# Sheet1.net
KiCad netlist of a schematic drawn in Altium Designer
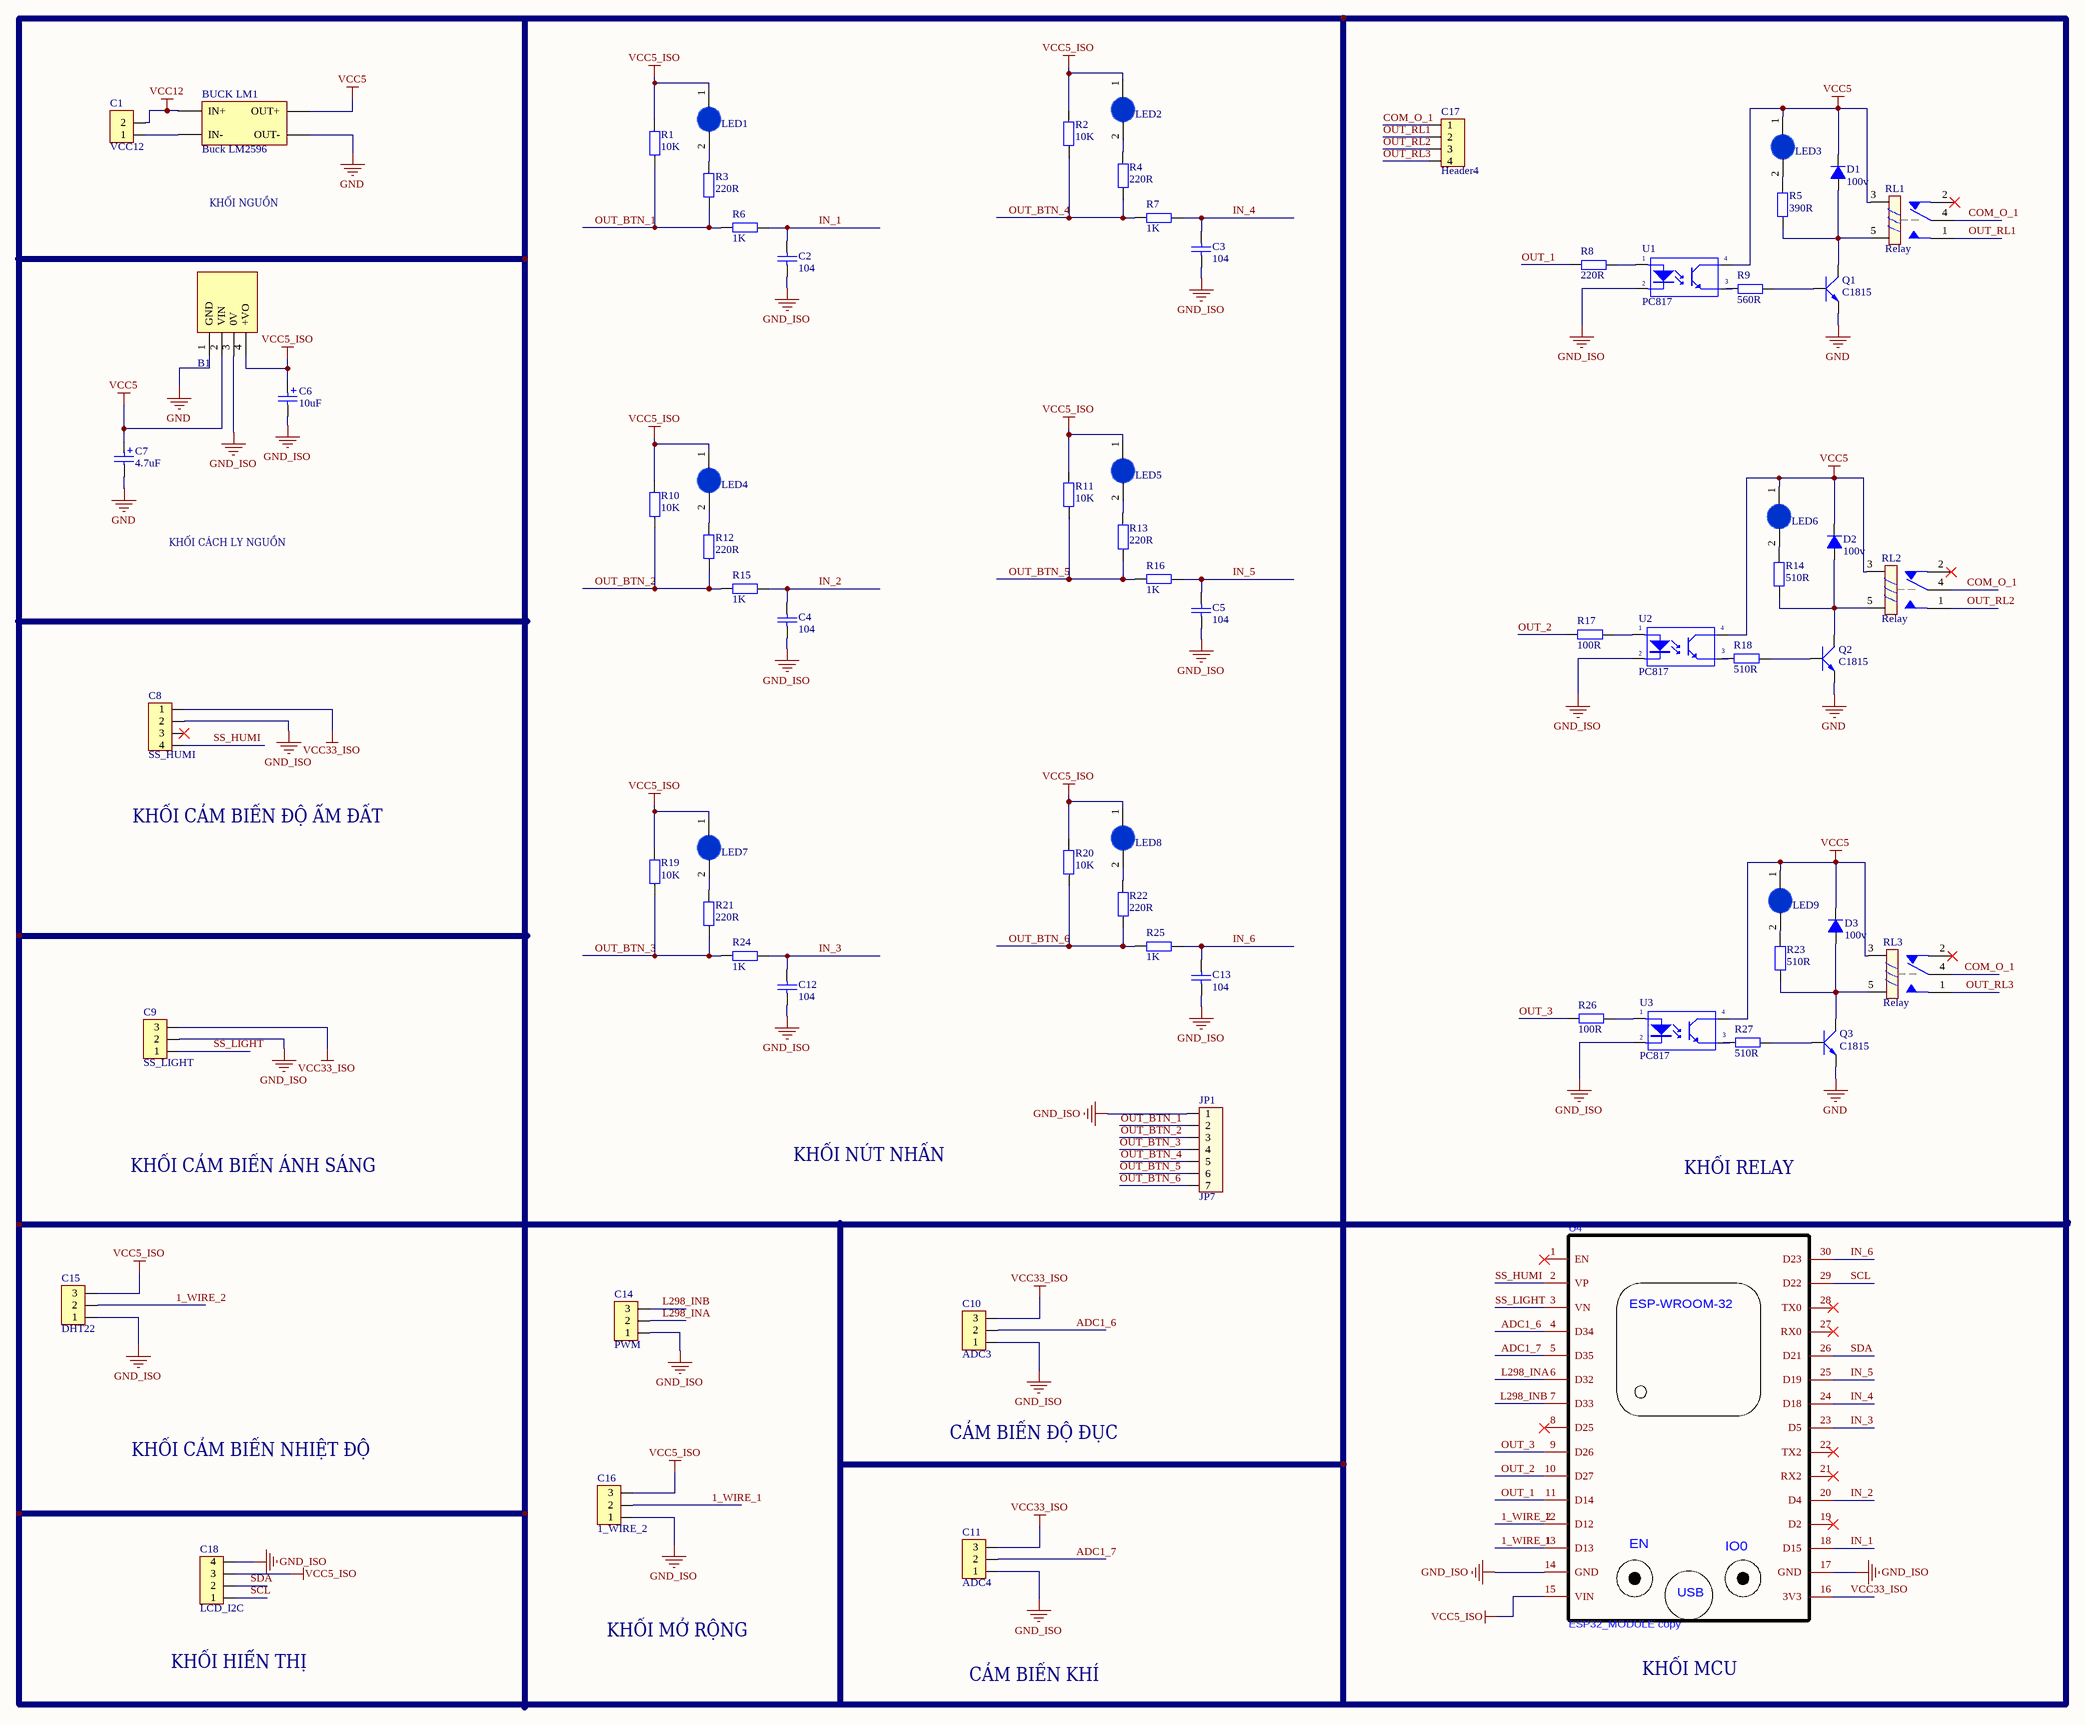
[diagram p0: Sheet1.SchDoc]

(export (version "E")
  (design (tool "Eeschema 10.0.6"))
  (components
    (comp (ref "B1")
      (value "B0505S1W")
      (footprint "B0505S1W")
      (description "Power Supply")
      (fields (field (name "MANUFACTURER_PART_NUMBER") "B0505S-1W"))
      (libsource (lib "myLib_v1") (part "B0505S1W"))
    )
    (comp (ref "BUCK LM1")
      (value "Buck LM2596")
      (footprint "BUCK LM2596")
      (libsource (lib "myLib_v1") (part "Buck LM2596"))
    )
    (comp (ref "C1")
      (value "VCC12")
      (footprint "Header2")
      (description "Header IDC, 2 x 1 Pin Vertical 2.54mm Pitch (Non-Boxed, Male)")
      (fields
        (field (name "MANUFACTURER") "Würth Elektronik eiSos GmbH")
        (field (name "PARTNO") "613002143121")
        (field (name "CREATED BY") "Karrer Zheng")
      )
      (libsource (lib "myLib_v1") (part "Header2"))
    )
    (comp (ref "C2")
      (value "104")
      (footprint "tu gom")
      (description "Cắm")
      (libsource (lib "Altium_Lib_by_KhueNguyenCreator") (part "Tu gom 104 50V"))
    )
    (comp (ref "C3")
      (value "104")
      (footprint "tu gom")
      (description "Cắm")
      (libsource (lib "Altium_Lib_by_KhueNguyenCreator") (part "Tu gom 104 50V"))
    )
    (comp (ref "C4")
      (value "104")
      (footprint "tu gom")
      (description "Cắm")
      (libsource (lib "Altium_Lib_by_KhueNguyenCreator") (part "Tu gom 104 50V"))
    )
    (comp (ref "C5")
      (value "104")
      (footprint "tu gom")
      (description "Cắm")
      (libsource (lib "Altium_Lib_by_KhueNguyenCreator") (part "Tu gom 104 50V"))
    )
    (comp (ref "C6")
      (value "10uF")
      (footprint "CP2/5")
      (description "Polarized Capacitor (Surface Mount)")
      (fields (field (name "Comment") "Cap Pol3") (field (name "PUBLISHER") "Altium Limited"))
      (libsource (lib "myLib_v1") (part "Cap Pol3"))
    )
    (comp (ref "C7")
      (value "4.7uF")
      (footprint "CP2/5")
      (description "Polarized Capacitor (Surface Mount)")
      (fields (field (name "Comment") "Cap Pol3") (field (name "PUBLISHER") "Altium Limited"))
      (libsource (lib "myLib_v1") (part "Cap Pol3"))
    )
    (comp (ref "C8")
      (value "SS_HUMI")
      (footprint "Header4")
      (description "Header IDC, 4 x 1 Pin Vertical 2.54mm Pitch (Non-Boxed, Male)")
      (fields
        (field (name "MANUFACTURER") "Würth Elektronik eiSos GmbH")
        (field (name "PARTNO") "613002143121")
        (field (name "CREATED BY") "Karrer Zheng")
      )
      (libsource (lib "myLib_v1") (part "Header4"))
    )
    (comp (ref "C9")
      (value "SS_LIGHT")
      (footprint "Header3")
      (description "Header IDC, 3 x 1 Pin Vertical 2.54mm Pitch (Non-Boxed, Male)")
      (fields
        (field (name "MANUFACTURER") "Würth Elektronik eiSos GmbH")
        (field (name "PARTNO") "613002143121")
        (field (name "CREATED BY") "Karrer Zheng")
      )
      (libsource (lib "myLib_v1") (part "Header3"))
    )
    (comp (ref "C10")
      (value "ADC3")
      (footprint "Header3")
      (description "Header IDC, 3 x 1 Pin Vertical 2.54mm Pitch (Non-Boxed, Male)")
      (fields
        (field (name "MANUFACTURER") "Würth Elektronik eiSos GmbH")
        (field (name "PARTNO") "613002143121")
        (field (name "CREATED BY") "Karrer Zheng")
      )
      (libsource (lib "myLib_v1") (part "Header3"))
    )
    (comp (ref "C11")
      (value "ADC4")
      (footprint "Header3")
      (description "Header IDC, 3 x 1 Pin Vertical 2.54mm Pitch (Non-Boxed, Male)")
      (fields
        (field (name "MANUFACTURER") "Würth Elektronik eiSos GmbH")
        (field (name "PARTNO") "613002143121")
        (field (name "CREATED BY") "Karrer Zheng")
      )
      (libsource (lib "myLib_v1") (part "Header3"))
    )
    (comp (ref "C12")
      (value "104")
      (footprint "tu gom")
      (description "Cắm")
      (libsource (lib "Altium_Lib_by_KhueNguyenCreator") (part "Tu gom 104 50V"))
    )
    (comp (ref "C13")
      (value "104")
      (footprint "tu gom")
      (description "Cắm")
      (libsource (lib "Altium_Lib_by_KhueNguyenCreator") (part "Tu gom 104 50V"))
    )
    (comp (ref "C14")
      (value "PWM")
      (footprint "Header3")
      (description "Header IDC, 3 x 1 Pin Vertical 2.54mm Pitch (Non-Boxed, Male)")
      (fields
        (field (name "MANUFACTURER") "Würth Elektronik eiSos GmbH")
        (field (name "PARTNO") "613002143121")
        (field (name "CREATED BY") "Karrer Zheng")
      )
      (libsource (lib "myLib_v1") (part "Header3"))
    )
    (comp (ref "C15")
      (value "DHT22")
      (footprint "Header3")
      (description "Header IDC, 3 x 1 Pin Vertical 2.54mm Pitch (Non-Boxed, Male)")
      (fields
        (field (name "MANUFACTURER") "Würth Elektronik eiSos GmbH")
        (field (name "PARTNO") "613002143121")
        (field (name "CREATED BY") "Karrer Zheng")
      )
      (libsource (lib "myLib_v1") (part "Header3"))
    )
    (comp (ref "C16")
      (value "1_WIRE_2")
      (footprint "Header3")
      (description "Header IDC, 3 x 1 Pin Vertical 2.54mm Pitch (Non-Boxed, Male)")
      (fields
        (field (name "MANUFACTURER") "Würth Elektronik eiSos GmbH")
        (field (name "PARTNO") "613002143121")
        (field (name "CREATED BY") "Karrer Zheng")
      )
      (libsource (lib "myLib_v1") (part "Header3"))
    )
    (comp (ref "C17")
      (value "Header4")
      (footprint "Header4")
      (description "Header IDC, 4 x 1 Pin Vertical 2.54mm Pitch (Non-Boxed, Male)")
      (fields
        (field (name "MANUFACTURER") "Würth Elektronik eiSos GmbH")
        (field (name "PARTNO") "613002143121")
        (field (name "CREATED BY") "Karrer Zheng")
      )
      (libsource (lib "") (part "Header4_2"))
    )
    (comp (ref "C18")
      (value "LCD_I2C")
      (footprint "Header4")
      (description "Header IDC, 4 x 1 Pin Vertical 2.54mm Pitch (Non-Boxed, Male)")
      (fields
        (field (name "MANUFACTURER") "Würth Elektronik eiSos GmbH")
        (field (name "PARTNO") "613002143121")
        (field (name "CREATED BY") "Karrer Zheng")
      )
      (libsource (lib "") (part "Header4_1"))
    )
    (comp (ref "D1")
      (value "100v")
      (footprint "DIODE 0.5A")
      (description "Cắm")
      (libsource (lib "Altium_Lib_by_KhueNguyenCreator") (part "Diode 1N4148"))
    )
    (comp (ref "D2")
      (value "100v")
      (footprint "DIODE 0.5A")
      (description "Cắm")
      (libsource (lib "Altium_Lib_by_KhueNguyenCreator") (part "Diode 1N4148"))
    )
    (comp (ref "D3")
      (value "100v")
      (footprint "DIODE 0.5A")
      (description "Cắm")
      (libsource (lib "Altium_Lib_by_KhueNguyenCreator") (part "Diode 1N4148"))
    )
    (comp (ref "JP1")
      (value "JP7")
      (footprint "Header7")
      (description "Connector 7")
      (libsource (lib "myLib_v1") (part "Header7"))
    )
    (comp (ref "LED1")
      (value "LED 3mm")
      (footprint "LED-3MM-BLUE")
      (description "Cắm")
      (libsource (lib "myLib_v1") (part "LED 3mm Xanh Duong"))
    )
    (comp (ref "LED2")
      (value "LED 3mm")
      (footprint "LED-3MM-BLUE")
      (description "Cắm")
      (libsource (lib "myLib_v1") (part "LED 3mm Xanh Duong"))
    )
    (comp (ref "LED3")
      (value "LED 3mm")
      (footprint "LED-3MM-BLUE")
      (description "Cắm")
      (libsource (lib "myLib_v1") (part "LED 3mm Xanh Duong"))
    )
    (comp (ref "LED4")
      (value "LED 3mm")
      (footprint "LED-3MM-BLUE")
      (description "Cắm")
      (libsource (lib "myLib_v1") (part "LED 3mm Xanh Duong"))
    )
    (comp (ref "LED5")
      (value "LED 3mm")
      (footprint "LED-3MM-BLUE")
      (description "Cắm")
      (libsource (lib "myLib_v1") (part "LED 3mm Xanh Duong"))
    )
    (comp (ref "LED6")
      (value "LED 3mm")
      (footprint "LED-3MM-BLUE")
      (description "Cắm")
      (libsource (lib "myLib_v1") (part "LED 3mm Xanh Duong"))
    )
    (comp (ref "LED7")
      (value "LED 3mm")
      (footprint "LED-3MM-BLUE")
      (description "Cắm")
      (libsource (lib "myLib_v1") (part "LED 3mm Xanh Duong"))
    )
    (comp (ref "LED8")
      (value "LED 3mm")
      (footprint "LED-3MM-BLUE")
      (description "Cắm")
      (libsource (lib "myLib_v1") (part "LED 3mm Xanh Duong"))
    )
    (comp (ref "LED9")
      (value "LED 3mm")
      (footprint "LED-3MM-BLUE")
      (description "Cắm")
      (libsource (lib "myLib_v1") (part "LED 3mm Xanh Duong"))
    )
    (comp (ref "Q1")
      (value "C1815")
      (footprint "C1815_cam")
      (description "NPN 600mW, ECB")
      (libsource (lib "myLib_v1") (part "C1815"))
    )
    (comp (ref "Q2")
      (value "C1815")
      (footprint "C1815_cam")
      (description "NPN 600mW, ECB")
      (libsource (lib "myLib_v1") (part "C1815"))
    )
    (comp (ref "Q3")
      (value "C1815")
      (footprint "C1815_cam")
      (description "NPN 600mW, ECB")
      (libsource (lib "myLib_v1") (part "C1815"))
    )
    (comp (ref "R1")
      (value "10K")
      (footprint "R1/4W")
      (description "Resistor 1/4W")
      (libsource (lib "myLib_v1") (part "R1/4W"))
    )
    (comp (ref "R2")
      (value "10K")
      (footprint "R1/4W")
      (description "Resistor 1/4W")
      (libsource (lib "myLib_v1") (part "R1/4W"))
    )
    (comp (ref "R3")
      (value "220R")
      (footprint "R1/4W")
      (description "Resistor 1/4W")
      (libsource (lib "myLib_v1") (part "R1/4W"))
    )
    (comp (ref "R4")
      (value "220R")
      (footprint "R1/4W")
      (description "Resistor 1/4W")
      (libsource (lib "myLib_v1") (part "R1/4W"))
    )
    (comp (ref "R5")
      (value "390R")
      (footprint "R1/4W")
      (description "Resistor 1/4W")
      (libsource (lib "myLib_v1") (part "R1/4W"))
    )
    (comp (ref "R6")
      (value "1K")
      (footprint "R1/4W")
      (description "Resistor 1/4W")
      (libsource (lib "myLib_v1") (part "R1/4W"))
    )
    (comp (ref "R7")
      (value "1K")
      (footprint "R1/4W")
      (description "Resistor 1/4W")
      (libsource (lib "myLib_v1") (part "R1/4W"))
    )
    (comp (ref "R8")
      (value "220R")
      (footprint "R1/4W")
      (description "Resistor 1/4W")
      (libsource (lib "myLib_v1") (part "R1/4W"))
    )
    (comp (ref "R9")
      (value "560R")
      (footprint "R1/4W")
      (description "Resistor 1/4W")
      (libsource (lib "myLib_v1") (part "R1/4W"))
    )
    (comp (ref "R10")
      (value "10K")
      (footprint "R1/4W")
      (description "Resistor 1/4W")
      (libsource (lib "myLib_v1") (part "R1/4W"))
    )
    (comp (ref "R11")
      (value "10K")
      (footprint "R1/4W")
      (description "Resistor 1/4W")
      (libsource (lib "myLib_v1") (part "R1/4W"))
    )
    (comp (ref "R12")
      (value "220R")
      (footprint "R1/4W")
      (description "Resistor 1/4W")
      (libsource (lib "myLib_v1") (part "R1/4W"))
    )
    (comp (ref "R13")
      (value "220R")
      (footprint "R1/4W")
      (description "Resistor 1/4W")
      (libsource (lib "myLib_v1") (part "R1/4W"))
    )
    (comp (ref "R14")
      (value "510R")
      (footprint "R1/4W")
      (description "Resistor 1/4W")
      (libsource (lib "myLib_v1") (part "R1/4W"))
    )
    (comp (ref "R15")
      (value "1K")
      (footprint "R1/4W")
      (description "Resistor 1/4W")
      (libsource (lib "myLib_v1") (part "R1/4W"))
    )
    (comp (ref "R16")
      (value "1K")
      (footprint "R1/4W")
      (description "Resistor 1/4W")
      (libsource (lib "myLib_v1") (part "R1/4W"))
    )
    (comp (ref "R17")
      (value "100R")
      (footprint "R1/4W")
      (description "Resistor 1/4W")
      (libsource (lib "myLib_v1") (part "R1/4W"))
    )
    (comp (ref "R18")
      (value "510R")
      (footprint "R1/4W")
      (description "Resistor 1/4W")
      (libsource (lib "myLib_v1") (part "R1/4W"))
    )
    (comp (ref "R19")
      (value "10K")
      (footprint "R1/4W")
      (description "Resistor 1/4W")
      (libsource (lib "myLib_v1") (part "R1/4W"))
    )
    (comp (ref "R20")
      (value "10K")
      (footprint "R1/4W")
      (description "Resistor 1/4W")
      (libsource (lib "myLib_v1") (part "R1/4W"))
    )
    (comp (ref "R21")
      (value "220R")
      (footprint "R1/4W")
      (description "Resistor 1/4W")
      (libsource (lib "myLib_v1") (part "R1/4W"))
    )
    (comp (ref "R22")
      (value "220R")
      (footprint "R1/4W")
      (description "Resistor 1/4W")
      (libsource (lib "myLib_v1") (part "R1/4W"))
    )
    (comp (ref "R23")
      (value "510R")
      (footprint "R1/4W")
      (description "Resistor 1/4W")
      (libsource (lib "myLib_v1") (part "R1/4W"))
    )
    (comp (ref "R24")
      (value "1K")
      (footprint "R1/4W")
      (description "Resistor 1/4W")
      (libsource (lib "myLib_v1") (part "R1/4W"))
    )
    (comp (ref "R25")
      (value "1K")
      (footprint "R1/4W")
      (description "Resistor 1/4W")
      (libsource (lib "myLib_v1") (part "R1/4W"))
    )
    (comp (ref "R26")
      (value "100R")
      (footprint "R1/4W")
      (description "Resistor 1/4W")
      (libsource (lib "myLib_v1") (part "R1/4W"))
    )
    (comp (ref "R27")
      (value "510R")
      (footprint "R1/4W")
      (description "Resistor 1/4W")
      (libsource (lib "myLib_v1") (part "R1/4W"))
    )
    (comp (ref "RL1")
      (value "Relay")
      (footprint "RELAY_SRA_05VDC_SL_C")
      (description "Relay 5 Chan")
      (libsource (lib "myLib_v1") (part "RL_SRA-05VDC-SL-C"))
    )
    (comp (ref "RL2")
      (value "Relay")
      (footprint "RELAY_SRA_05VDC_SL_C")
      (description "Relay 5 Chan")
      (libsource (lib "myLib_v1") (part "RL_SRA-05VDC-SL-C"))
    )
    (comp (ref "RL3")
      (value "Relay")
      (footprint "RELAY_SRA_05VDC_SL_C")
      (description "Relay 5 Chan")
      (libsource (lib "myLib_v1") (part "RL_SRA-05VDC-SL-C"))
    )
    (comp (ref "U1")
      (value "PC817")
      (footprint "DIP4/W0.3")
      (description "Single Opto")
      (libsource (lib "myLib_v1") (part "PC817"))
    )
    (comp (ref "U2")
      (value "PC817")
      (footprint "DIP4/W0.3")
      (description "Single Opto")
      (libsource (lib "myLib_v1") (part "PC817"))
    )
    (comp (ref "U3")
      (value "PC817")
      (footprint "DIP4/W0.3")
      (description "Single Opto")
      (libsource (lib "myLib_v1") (part "PC817"))
    )
    (comp (ref "U4")
      (value "ESP32_MODULE copy")
      (footprint "ESP32-WIFIMODULE-FOOTPRINT")
      (libsource (lib "myLib_v1") (part "ESP32_MODULE copy"))
    )
  )
  (nets
    (net (code "1") (name "/1_WIRE_1") (class "Default")
      (node (ref "C16") (pin "2") (pinfunction "2_2") (pintype "passive"))
      (node (ref "U4") (pin "13") (pinfunction "D13_13") (pintype "passive"))
    )
    (net (code "2") (name "/1_WIRE_2") (class "Default")
      (node (ref "C15") (pin "2") (pinfunction "2_2") (pintype "passive"))
      (node (ref "U4") (pin "12") (pinfunction "D12_12") (pintype "passive"))
    )
    (net (code "3") (name "/ADC1_6") (class "Default")
      (node (ref "C10") (pin "2") (pinfunction "2_2") (pintype "passive"))
      (node (ref "U4") (pin "4") (pinfunction "D34_4") (pintype "passive"))
    )
    (net (code "4") (name "/ADC1_7") (class "Default")
      (node (ref "C11") (pin "2") (pinfunction "2_2") (pintype "passive"))
      (node (ref "U4") (pin "5") (pinfunction "D35_5") (pintype "passive"))
    )
    (net (code "5") (name "/COM_O_1") (class "Default")
      (node (ref "C17") (pin "1") (pinfunction "1_1") (pintype "passive"))
      (node (ref "RL1") (pin "4") (pinfunction "4_4") (pintype "passive"))
      (node (ref "RL2") (pin "4") (pinfunction "4_4") (pintype "passive"))
      (node (ref "RL3") (pin "4") (pinfunction "4_4") (pintype "passive"))
    )
    (net (code "6") (name "/IN_1") (class "Default")
      (node (ref "C2") (pin "1") (pinfunction "1_1") (pintype "passive"))
      (node (ref "R6") (pin "1") (pinfunction "1_1") (pintype "passive"))
      (node (ref "U4") (pin "18") (pinfunction "D15_18") (pintype "passive"))
    )
    (net (code "7") (name "/IN_2") (class "Default")
      (node (ref "C4") (pin "1") (pinfunction "1_1") (pintype "passive"))
      (node (ref "R15") (pin "1") (pinfunction "1_1") (pintype "passive"))
      (node (ref "U4") (pin "20") (pinfunction "D4_20") (pintype "passive"))
    )
    (net (code "8") (name "/IN_3") (class "Default")
      (node (ref "C12") (pin "1") (pinfunction "1_1") (pintype "passive"))
      (node (ref "R24") (pin "1") (pinfunction "1_1") (pintype "passive"))
      (node (ref "U4") (pin "23") (pinfunction "D5_23") (pintype "passive"))
    )
    (net (code "9") (name "/IN_4") (class "Default")
      (node (ref "C3") (pin "1") (pinfunction "1_1") (pintype "passive"))
      (node (ref "R7") (pin "1") (pinfunction "1_1") (pintype "passive"))
      (node (ref "U4") (pin "24") (pinfunction "D18_24") (pintype "passive"))
    )
    (net (code "10") (name "/IN_5") (class "Default")
      (node (ref "C5") (pin "1") (pinfunction "1_1") (pintype "passive"))
      (node (ref "R16") (pin "1") (pinfunction "1_1") (pintype "passive"))
      (node (ref "U4") (pin "25") (pinfunction "D19_25") (pintype "passive"))
    )
    (net (code "11") (name "/IN_6") (class "Default")
      (node (ref "C13") (pin "1") (pinfunction "1_1") (pintype "passive"))
      (node (ref "R25") (pin "1") (pinfunction "1_1") (pintype "passive"))
      (node (ref "U4") (pin "30") (pinfunction "D23_30") (pintype "passive"))
    )
    (net (code "12") (name "/L298_INA") (class "Default")
      (node (ref "C14") (pin "2") (pinfunction "2_2") (pintype "passive"))
      (node (ref "U4") (pin "6") (pinfunction "D32_6") (pintype "passive"))
    )
    (net (code "13") (name "/L298_INB") (class "Default")
      (node (ref "C14") (pin "3") (pinfunction "3_3") (pintype "passive"))
      (node (ref "U4") (pin "7") (pinfunction "D33_7") (pintype "passive"))
    )
    (net (code "14") (name "/OUT_1") (class "Default")
      (node (ref "R8") (pin "1") (pinfunction "1_1") (pintype "passive"))
      (node (ref "U4") (pin "11") (pinfunction "D14_11") (pintype "passive"))
    )
    (net (code "15") (name "/OUT_2") (class "Default")
      (node (ref "R17") (pin "1") (pinfunction "1_1") (pintype "passive"))
      (node (ref "U4") (pin "10") (pinfunction "D27_10") (pintype "passive"))
    )
    (net (code "16") (name "/OUT_3") (class "Default")
      (node (ref "R26") (pin "1") (pinfunction "1_1") (pintype "passive"))
      (node (ref "U4") (pin "9") (pinfunction "D26_9") (pintype "passive"))
    )
    (net (code "17") (name "/OUT_BTN_1") (class "Default")
      (node (ref "JP1") (pin "2") (pinfunction "2_2") (pintype "passive"))
      (node (ref "R1") (pin "1") (pinfunction "1_1") (pintype "passive"))
      (node (ref "R3") (pin "1") (pinfunction "1_1") (pintype "passive"))
      (node (ref "R6") (pin "2") (pinfunction "2_2") (pintype "passive"))
    )
    (net (code "18") (name "/OUT_BTN_2") (class "Default")
      (node (ref "JP1") (pin "3") (pinfunction "3_3") (pintype "passive"))
      (node (ref "R10") (pin "1") (pinfunction "1_1") (pintype "passive"))
      (node (ref "R12") (pin "1") (pinfunction "1_1") (pintype "passive"))
      (node (ref "R15") (pin "2") (pinfunction "2_2") (pintype "passive"))
    )
    (net (code "19") (name "/OUT_BTN_3") (class "Default")
      (node (ref "JP1") (pin "4") (pinfunction "4_4") (pintype "passive"))
      (node (ref "R19") (pin "1") (pinfunction "1_1") (pintype "passive"))
      (node (ref "R21") (pin "1") (pinfunction "1_1") (pintype "passive"))
      (node (ref "R24") (pin "2") (pinfunction "2_2") (pintype "passive"))
    )
    (net (code "20") (name "/OUT_BTN_4") (class "Default")
      (node (ref "JP1") (pin "5") (pinfunction "5_5") (pintype "passive"))
      (node (ref "R2") (pin "1") (pinfunction "1_1") (pintype "passive"))
      (node (ref "R4") (pin "1") (pinfunction "1_1") (pintype "passive"))
      (node (ref "R7") (pin "2") (pinfunction "2_2") (pintype "passive"))
    )
    (net (code "21") (name "/OUT_BTN_5") (class "Default")
      (node (ref "JP1") (pin "6") (pinfunction "6_6") (pintype "passive"))
      (node (ref "R11") (pin "1") (pinfunction "1_1") (pintype "passive"))
      (node (ref "R13") (pin "1") (pinfunction "1_1") (pintype "passive"))
      (node (ref "R16") (pin "2") (pinfunction "2_2") (pintype "passive"))
    )
    (net (code "22") (name "/OUT_BTN_6") (class "Default")
      (node (ref "JP1") (pin "7") (pinfunction "7_7") (pintype "passive"))
      (node (ref "R20") (pin "1") (pinfunction "1_1") (pintype "passive"))
      (node (ref "R22") (pin "1") (pinfunction "1_1") (pintype "passive"))
      (node (ref "R25") (pin "2") (pinfunction "2_2") (pintype "passive"))
    )
    (net (code "23") (name "/OUT_RL1") (class "Default")
      (node (ref "C17") (pin "2") (pinfunction "2_2") (pintype "passive"))
      (node (ref "RL1") (pin "1") (pinfunction "1_1") (pintype "passive"))
    )
    (net (code "24") (name "/OUT_RL2") (class "Default")
      (node (ref "C17") (pin "3") (pinfunction "3_3") (pintype "passive"))
      (node (ref "RL2") (pin "1") (pinfunction "1_1") (pintype "passive"))
    )
    (net (code "25") (name "/OUT_RL3") (class "Default")
      (node (ref "C17") (pin "4") (pinfunction "4_4") (pintype "passive"))
      (node (ref "RL3") (pin "1") (pinfunction "1_1") (pintype "passive"))
    )
    (net (code "26") (name "/SCL") (class "Default")
      (node (ref "C18") (pin "1") (pinfunction "1_1") (pintype "passive"))
      (node (ref "U4") (pin "29") (pinfunction "D22_29") (pintype "passive"))
    )
    (net (code "27") (name "/SDA") (class "Default")
      (node (ref "C18") (pin "2") (pinfunction "2_2") (pintype "passive"))
      (node (ref "U4") (pin "26") (pinfunction "D21_26") (pintype "passive"))
    )
    (net (code "28") (name "/SS_HUMI") (class "Default")
      (node (ref "C8") (pin "4") (pinfunction "4_4") (pintype "passive"))
      (node (ref "U4") (pin "2") (pinfunction "VP_2") (pintype "passive"))
    )
    (net (code "29") (name "/SS_LIGHT") (class "Default")
      (node (ref "C9") (pin "1") (pinfunction "1_1") (pintype "passive"))
      (node (ref "U4") (pin "3") (pinfunction "VN_3") (pintype "passive"))
    )
    (net (code "30") (name "GND") (class "Default")
      (node (ref "B1") (pin "1") (pinfunction "GND_1") (pintype "passive"))
      (node (ref "BUCK LM1") (pin "3") (pinfunction "OUT-_3") (pintype "passive"))
      (node (ref "C7") (pin "2") (pinfunction "2_2") (pintype "passive"))
      (node (ref "Q1") (pin "1") (pinfunction "E_1") (pintype "passive"))
      (node (ref "Q2") (pin "1") (pinfunction "E_1") (pintype "passive"))
      (node (ref "Q3") (pin "1") (pinfunction "E_1") (pintype "passive"))
    )
    (net (code "31") (name "GND_ISO") (class "Default")
      (node (ref "B1") (pin "3") (pinfunction "0V_3") (pintype "passive"))
      (node (ref "C10") (pin "1") (pinfunction "1_1") (pintype "passive"))
      (node (ref "C11") (pin "1") (pinfunction "1_1") (pintype "passive"))
      (node (ref "C12") (pin "2") (pinfunction "2_2") (pintype "passive"))
      (node (ref "C13") (pin "2") (pinfunction "2_2") (pintype "passive"))
      (node (ref "C14") (pin "1") (pinfunction "1_1") (pintype "passive"))
      (node (ref "C15") (pin "1") (pinfunction "1_1") (pintype "passive"))
      (node (ref "C16") (pin "1") (pinfunction "1_1") (pintype "passive"))
      (node (ref "C18") (pin "4") (pinfunction "4_4") (pintype "passive"))
      (node (ref "C2") (pin "2") (pinfunction "2_2") (pintype "passive"))
      (node (ref "C3") (pin "2") (pinfunction "2_2") (pintype "passive"))
      (node (ref "C4") (pin "2") (pinfunction "2_2") (pintype "passive"))
      (node (ref "C5") (pin "2") (pinfunction "2_2") (pintype "passive"))
      (node (ref "C6") (pin "2") (pinfunction "2_2") (pintype "passive"))
      (node (ref "C8") (pin "2") (pinfunction "2_2") (pintype "passive"))
      (node (ref "C9") (pin "2") (pinfunction "2_2") (pintype "passive"))
      (node (ref "JP1") (pin "1") (pinfunction "1_1") (pintype "passive"))
      (node (ref "U1") (pin "2") (pinfunction "K_2") (pintype "passive"))
      (node (ref "U2") (pin "2") (pinfunction "K_2") (pintype "passive"))
      (node (ref "U3") (pin "2") (pinfunction "K_2") (pintype "passive"))
      (node (ref "U4") (pin "14") (pinfunction "GND_14") (pintype "passive"))
      (node (ref "U4") (pin "17") (pinfunction "GND_17") (pintype "passive"))
    )
    (net (code "32") (name "Net-(BUCK LM1-IN-)") (class "Default")
      (node (ref "BUCK LM1") (pin "2") (pinfunction "IN-_2") (pintype "passive"))
      (node (ref "C1") (pin "1") (pinfunction "1_1") (pintype "passive"))
    )
    (net (code "33") (name "Net-(D1-A)") (class "Default")
      (node (ref "D1") (pin "1") (pinfunction "A_1") (pintype "passive"))
      (node (ref "Q1") (pin "2") (pinfunction "C_2") (pintype "passive"))
      (node (ref "R5") (pin "2") (pinfunction "2_2") (pintype "passive"))
      (node (ref "RL1") (pin "5") (pinfunction "5_5") (pintype "passive"))
    )
    (net (code "34") (name "Net-(D2-A)") (class "Default")
      (node (ref "D2") (pin "1") (pinfunction "A_1") (pintype "passive"))
      (node (ref "Q2") (pin "2") (pinfunction "C_2") (pintype "passive"))
      (node (ref "R14") (pin "2") (pinfunction "2_2") (pintype "passive"))
      (node (ref "RL2") (pin "5") (pinfunction "5_5") (pintype "passive"))
    )
    (net (code "35") (name "Net-(D3-A)") (class "Default")
      (node (ref "D3") (pin "1") (pinfunction "A_1") (pintype "passive"))
      (node (ref "Q3") (pin "2") (pinfunction "C_2") (pintype "passive"))
      (node (ref "R23") (pin "2") (pinfunction "2_2") (pintype "passive"))
      (node (ref "RL3") (pin "5") (pinfunction "5_5") (pintype "passive"))
    )
    (net (code "36") (name "Net-(LED1-K)") (class "Default")
      (node (ref "LED1") (pin "2") (pinfunction "K_2") (pintype "passive"))
      (node (ref "R3") (pin "2") (pinfunction "2_2") (pintype "passive"))
    )
    (net (code "37") (name "Net-(LED2-K)") (class "Default")
      (node (ref "LED2") (pin "2") (pinfunction "K_2") (pintype "passive"))
      (node (ref "R4") (pin "2") (pinfunction "2_2") (pintype "passive"))
    )
    (net (code "38") (name "Net-(LED3-K)") (class "Default")
      (node (ref "LED3") (pin "2") (pinfunction "K_2") (pintype "passive"))
      (node (ref "R5") (pin "1") (pinfunction "1_1") (pintype "passive"))
    )
    (net (code "39") (name "Net-(LED4-K)") (class "Default")
      (node (ref "LED4") (pin "2") (pinfunction "K_2") (pintype "passive"))
      (node (ref "R12") (pin "2") (pinfunction "2_2") (pintype "passive"))
    )
    (net (code "40") (name "Net-(LED5-K)") (class "Default")
      (node (ref "LED5") (pin "2") (pinfunction "K_2") (pintype "passive"))
      (node (ref "R13") (pin "2") (pinfunction "2_2") (pintype "passive"))
    )
    (net (code "41") (name "Net-(LED6-K)") (class "Default")
      (node (ref "LED6") (pin "2") (pinfunction "K_2") (pintype "passive"))
      (node (ref "R14") (pin "1") (pinfunction "1_1") (pintype "passive"))
    )
    (net (code "42") (name "Net-(LED7-K)") (class "Default")
      (node (ref "LED7") (pin "2") (pinfunction "K_2") (pintype "passive"))
      (node (ref "R21") (pin "2") (pinfunction "2_2") (pintype "passive"))
    )
    (net (code "43") (name "Net-(LED8-K)") (class "Default")
      (node (ref "LED8") (pin "2") (pinfunction "K_2") (pintype "passive"))
      (node (ref "R22") (pin "2") (pinfunction "2_2") (pintype "passive"))
    )
    (net (code "44") (name "Net-(LED9-K)") (class "Default")
      (node (ref "LED9") (pin "2") (pinfunction "K_2") (pintype "passive"))
      (node (ref "R23") (pin "1") (pinfunction "1_1") (pintype "passive"))
    )
    (net (code "45") (name "Net-(Q1-B)") (class "Default")
      (node (ref "Q1") (pin "3") (pinfunction "B_3") (pintype "passive"))
      (node (ref "R9") (pin "2") (pinfunction "2_2") (pintype "passive"))
    )
    (net (code "46") (name "Net-(Q2-B)") (class "Default")
      (node (ref "Q2") (pin "3") (pinfunction "B_3") (pintype "passive"))
      (node (ref "R18") (pin "2") (pinfunction "2_2") (pintype "passive"))
    )
    (net (code "47") (name "Net-(Q3-B)") (class "Default")
      (node (ref "Q3") (pin "3") (pinfunction "B_3") (pintype "passive"))
      (node (ref "R27") (pin "2") (pinfunction "2_2") (pintype "passive"))
    )
    (net (code "48") (name "Net-(U1-A)") (class "Default")
      (node (ref "R8") (pin "2") (pinfunction "2_2") (pintype "passive"))
      (node (ref "U1") (pin "1") (pinfunction "A_1") (pintype "passive"))
    )
    (net (code "49") (name "Net-(U1-E)") (class "Default")
      (node (ref "R9") (pin "1") (pinfunction "1_1") (pintype "passive"))
      (node (ref "U1") (pin "3") (pinfunction "E_3") (pintype "passive"))
    )
    (net (code "50") (name "Net-(U2-A)") (class "Default")
      (node (ref "R17") (pin "2") (pinfunction "2_2") (pintype "passive"))
      (node (ref "U2") (pin "1") (pinfunction "A_1") (pintype "passive"))
    )
    (net (code "51") (name "Net-(U2-E)") (class "Default")
      (node (ref "R18") (pin "1") (pinfunction "1_1") (pintype "passive"))
      (node (ref "U2") (pin "3") (pinfunction "E_3") (pintype "passive"))
    )
    (net (code "52") (name "Net-(U3-A)") (class "Default")
      (node (ref "R26") (pin "2") (pinfunction "2_2") (pintype "passive"))
      (node (ref "U3") (pin "1") (pinfunction "A_1") (pintype "passive"))
    )
    (net (code "53") (name "Net-(U3-E)") (class "Default")
      (node (ref "R27") (pin "1") (pinfunction "1_1") (pintype "passive"))
      (node (ref "U3") (pin "3") (pinfunction "E_3") (pintype "passive"))
    )
    (net (code "54") (name "VCC5") (class "Default")
      (node (ref "B1") (pin "2") (pinfunction "VIN_2") (pintype "passive"))
      (node (ref "BUCK LM1") (pin "4") (pinfunction "OUT+_4") (pintype "passive"))
      (node (ref "C7") (pin "1") (pinfunction "1_1") (pintype "passive"))
      (node (ref "D1") (pin "2") (pinfunction "K_2") (pintype "passive"))
      (node (ref "D2") (pin "2") (pinfunction "K_2") (pintype "passive"))
      (node (ref "D3") (pin "2") (pinfunction "K_2") (pintype "passive"))
      (node (ref "LED3") (pin "1") (pinfunction "A_1") (pintype "passive"))
      (node (ref "LED6") (pin "1") (pinfunction "A_1") (pintype "passive"))
      (node (ref "LED9") (pin "1") (pinfunction "A_1") (pintype "passive"))
      (node (ref "RL1") (pin "3") (pinfunction "3_3") (pintype "passive"))
      (node (ref "RL2") (pin "3") (pinfunction "3_3") (pintype "passive"))
      (node (ref "RL3") (pin "3") (pinfunction "3_3") (pintype "passive"))
      (node (ref "U1") (pin "4") (pinfunction "C_4") (pintype "passive"))
      (node (ref "U2") (pin "4") (pinfunction "C_4") (pintype "passive"))
      (node (ref "U3") (pin "4") (pinfunction "C_4") (pintype "passive"))
    )
    (net (code "55") (name "VCC5_ISO") (class "Default")
      (node (ref "B1") (pin "4") (pinfunction "+VO_4") (pintype "passive"))
      (node (ref "C15") (pin "3") (pinfunction "3_3") (pintype "passive"))
      (node (ref "C16") (pin "3") (pinfunction "3_3") (pintype "passive"))
      (node (ref "C18") (pin "3") (pinfunction "3_3") (pintype "passive"))
      (node (ref "C6") (pin "1") (pinfunction "1_1") (pintype "passive"))
      (node (ref "LED1") (pin "1") (pinfunction "A_1") (pintype "passive"))
      (node (ref "LED2") (pin "1") (pinfunction "A_1") (pintype "passive"))
      (node (ref "LED4") (pin "1") (pinfunction "A_1") (pintype "passive"))
      (node (ref "LED5") (pin "1") (pinfunction "A_1") (pintype "passive"))
      (node (ref "LED7") (pin "1") (pinfunction "A_1") (pintype "passive"))
      (node (ref "LED8") (pin "1") (pinfunction "A_1") (pintype "passive"))
      (node (ref "R1") (pin "2") (pinfunction "2_2") (pintype "passive"))
      (node (ref "R10") (pin "2") (pinfunction "2_2") (pintype "passive"))
      (node (ref "R11") (pin "2") (pinfunction "2_2") (pintype "passive"))
      (node (ref "R19") (pin "2") (pinfunction "2_2") (pintype "passive"))
      (node (ref "R2") (pin "2") (pinfunction "2_2") (pintype "passive"))
      (node (ref "R20") (pin "2") (pinfunction "2_2") (pintype "passive"))
      (node (ref "U4") (pin "15") (pinfunction "VIN_15") (pintype "passive"))
    )
    (net (code "56") (name "VCC12") (class "Default")
      (node (ref "BUCK LM1") (pin "1") (pinfunction "IN+_1") (pintype "passive"))
      (node (ref "C1") (pin "2") (pinfunction "2_2") (pintype "passive"))
    )
    (net (code "57") (name "VCC33_ISO") (class "Default")
      (node (ref "C10") (pin "3") (pinfunction "3_3") (pintype "passive"))
      (node (ref "C11") (pin "3") (pinfunction "3_3") (pintype "passive"))
      (node (ref "C8") (pin "1") (pinfunction "1_1") (pintype "passive"))
      (node (ref "C9") (pin "3") (pinfunction "3_3") (pintype "passive"))
      (node (ref "U4") (pin "16") (pinfunction "3V3_16") (pintype "passive"))
    )
    (net (code "58") (name "unconnected-(C8-Pad3)") (class "Default")
      (node (ref "C8") (pin "3") (pinfunction "3_3") (pintype "passive+no_connect"))
    )
    (net (code "59") (name "unconnected-(RL1-Pad2)") (class "Default")
      (node (ref "RL1") (pin "2") (pinfunction "2_2") (pintype "passive+no_connect"))
    )
    (net (code "60") (name "unconnected-(RL2-Pad2)") (class "Default")
      (node (ref "RL2") (pin "2") (pinfunction "2_2") (pintype "passive+no_connect"))
    )
    (net (code "61") (name "unconnected-(RL3-Pad2)") (class "Default")
      (node (ref "RL3") (pin "2") (pinfunction "2_2") (pintype "passive+no_connect"))
    )
    (net (code "62") (name "unconnected-(U4-D2-Pad19)") (class "Default")
      (node (ref "U4") (pin "19") (pinfunction "D2_19") (pintype "passive+no_connect"))
    )
    (net (code "63") (name "unconnected-(U4-D25-Pad8)") (class "Default")
      (node (ref "U4") (pin "8") (pinfunction "D25_8") (pintype "passive+no_connect"))
    )
    (net (code "64") (name "unconnected-(U4-EN-Pad1)") (class "Default")
      (node (ref "U4") (pin "1") (pinfunction "EN_1") (pintype "passive+no_connect"))
    )
    (net (code "65") (name "unconnected-(U4-RX0-Pad27)") (class "Default")
      (node (ref "U4") (pin "27") (pinfunction "RX0_27") (pintype "passive+no_connect"))
    )
    (net (code "66") (name "unconnected-(U4-RX2-Pad21)") (class "Default")
      (node (ref "U4") (pin "21") (pinfunction "RX2_21") (pintype "passive+no_connect"))
    )
    (net (code "67") (name "unconnected-(U4-TX0-Pad28)") (class "Default")
      (node (ref "U4") (pin "28") (pinfunction "TX0_28") (pintype "passive+no_connect"))
    )
    (net (code "68") (name "unconnected-(U4-TX2-Pad22)") (class "Default")
      (node (ref "U4") (pin "22") (pinfunction "TX2_22") (pintype "passive+no_connect"))
    )
  )
)
